# FUSB302-Breakout-ODG_Eagle7_X.net
KiCad netlist of a schematic drawn in EAGLE
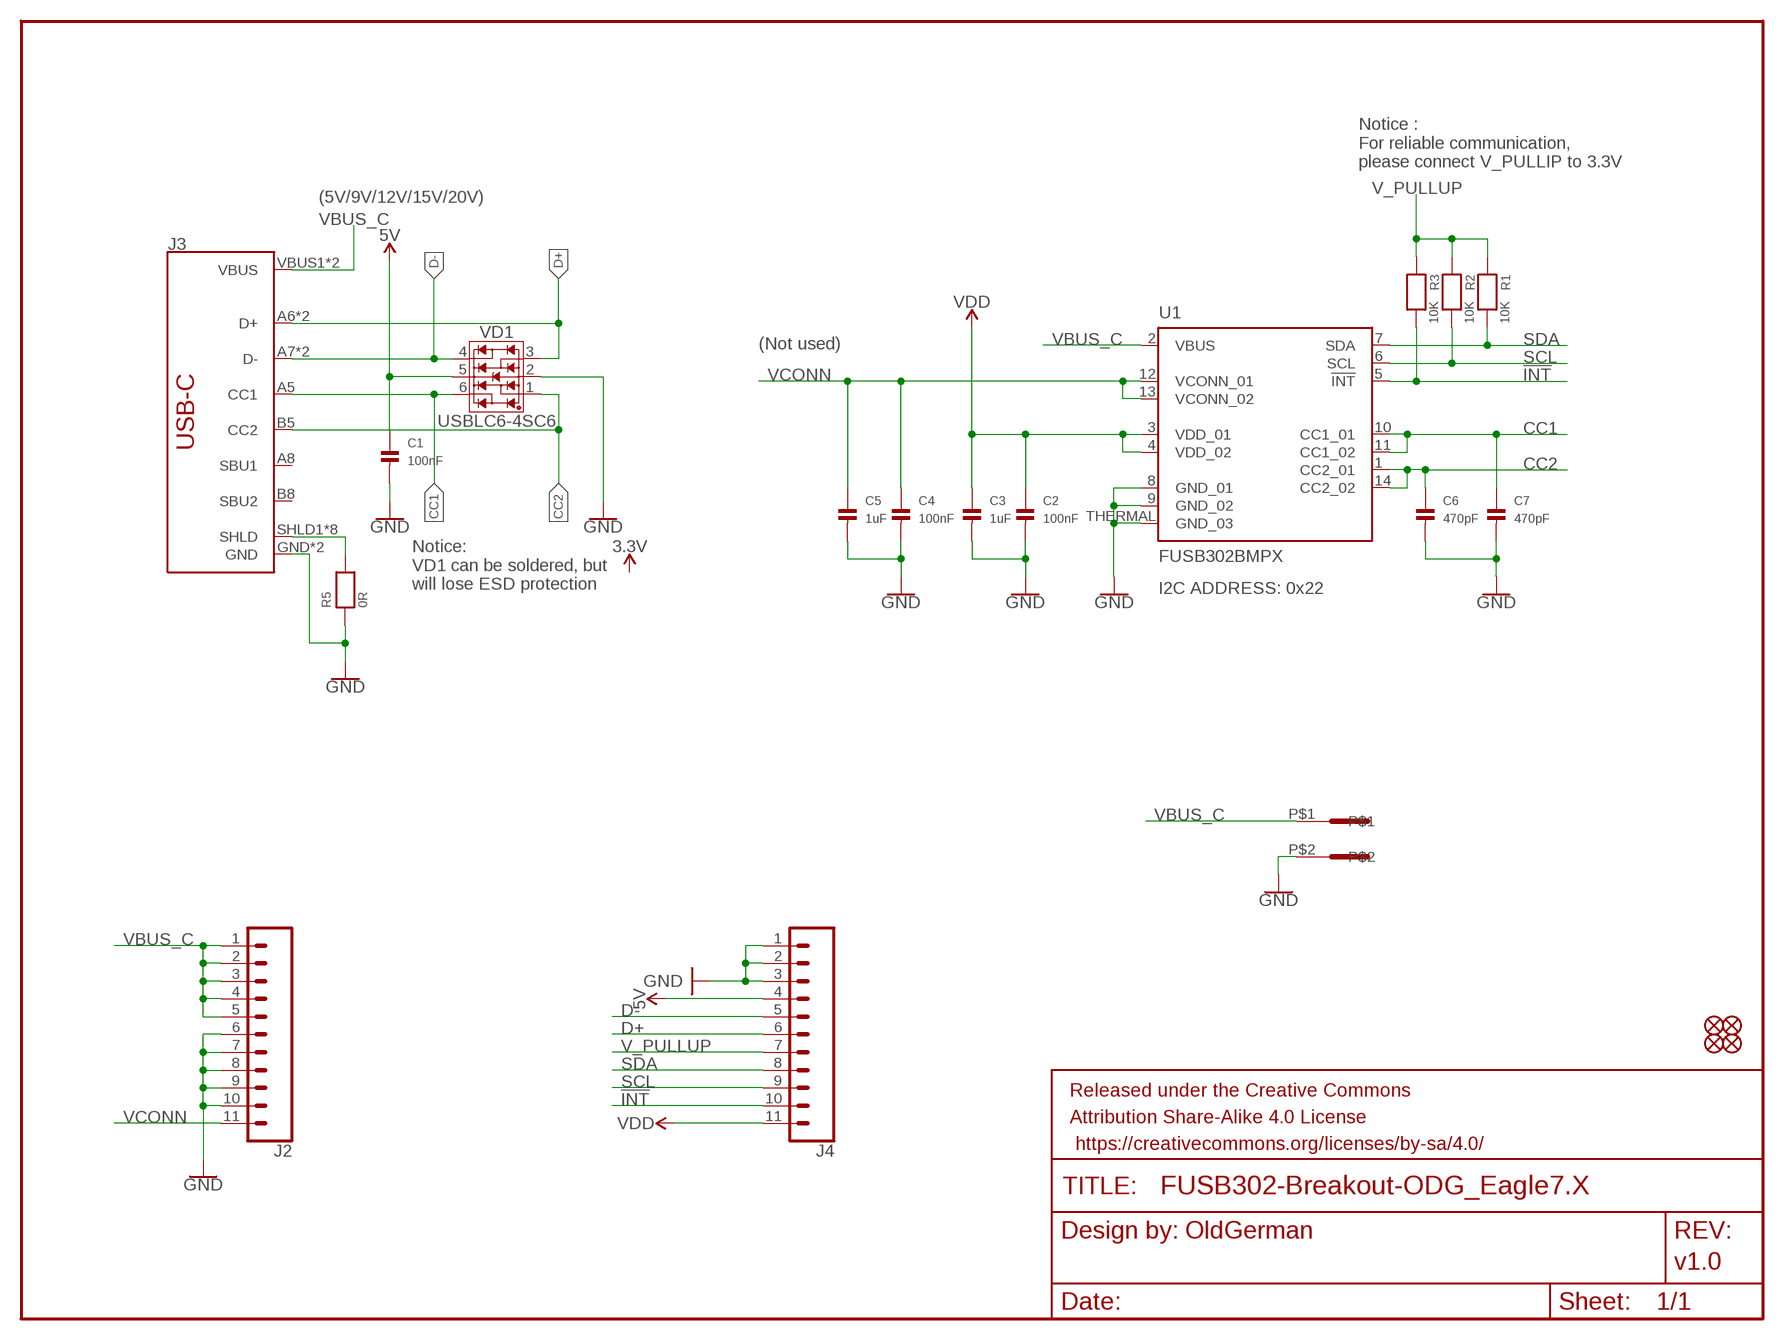
[diagram p0: schematic, sheet 1]

(export (version "E")
  (design (tool "Eeschema 10.0.6"))
  (components
    (comp (ref "C1")
      (value "100nF")
      (footprint "eagle-import:0603")
      (libsource (lib "eagle-import") (part "CAP_CERAMIC0603"))
    )
    (comp (ref "C2")
      (value "100nF")
      (footprint "eagle-import:0603")
      (libsource (lib "eagle-import") (part "CAP_CERAMIC0603"))
    )
    (comp (ref "C3")
      (value "1uF")
      (footprint "eagle-import:0603")
      (libsource (lib "eagle-import") (part "CAP_CERAMIC0603"))
    )
    (comp (ref "C4")
      (value "100nF")
      (footprint "eagle-import:0603")
      (libsource (lib "eagle-import") (part "CAP_CERAMIC0603"))
    )
    (comp (ref "C5")
      (value "1uF")
      (footprint "eagle-import:0603")
      (libsource (lib "eagle-import") (part "CAP_CERAMIC0603"))
    )
    (comp (ref "C6")
      (value "470pF")
      (footprint "eagle-import:0603")
      (libsource (lib "eagle-import") (part "CAP_CERAMIC0603"))
    )
    (comp (ref "C7")
      (value "470pF")
      (footprint "eagle-import:0603")
      (libsource (lib "eagle-import") (part "CAP_CERAMIC0603"))
    )
    (comp (ref "FD5")
      (value "FIDUCIAL_MINI1X2")
      (footprint "eagle-import:FIDUCIAL-1X2")
      (libsource (lib "eagle-import") (part "FIDUCIAL_MINI1X2"))
    )
    (comp (ref "FD6")
      (value "FIDUCIAL_MINI1X2")
      (footprint "eagle-import:FIDUCIAL-1X2")
      (libsource (lib "eagle-import") (part "FIDUCIAL_MINI1X2"))
    )
    (comp (ref "FD7")
      (value "FIDUCIAL_MINI1X2")
      (footprint "eagle-import:FIDUCIAL-1X2")
      (libsource (lib "eagle-import") (part "FIDUCIAL_MINI1X2"))
    )
    (comp (ref "FD8")
      (value "FIDUCIAL_MINI1X2")
      (footprint "eagle-import:FIDUCIAL-1X2")
      (libsource (lib "eagle-import") (part "FIDUCIAL_MINI1X2"))
    )
    (comp (ref "FRAME2")
      (value "FRAME-LETTER")
      (footprint "eagle-import:CREATIVE_COMMONS")
      (libsource (lib "eagle-import") (part "FRAME-LETTER"))
    )
    (comp (ref "J2")
      (value "CONN_11")
      (footprint "eagle-import:1X11")
      (libsource (lib "eagle-import") (part "CONN_11"))
    )
    (comp (ref "J3")
      (value "USB_C_LONG-SYMBOL2-LAYER")
      (footprint "eagle-import:USB-C-16P")
      (libsource (lib "eagle-import") (part "USB_C_LONG-SYMBOL2-LAYER"))
    )
    (comp (ref "J4")
      (value "CONN_11")
      (footprint "eagle-import:1X11")
      (libsource (lib "eagle-import") (part "CONN_11"))
    )
    (comp (ref "R1")
      (value "10K")
      (footprint "eagle-import:0603")
      (libsource (lib "eagle-import") (part "RESISTOR0603"))
    )
    (comp (ref "R2")
      (value "10K")
      (footprint "eagle-import:0603")
      (libsource (lib "eagle-import") (part "RESISTOR0603"))
    )
    (comp (ref "R3")
      (value "10K")
      (footprint "eagle-import:0603")
      (libsource (lib "eagle-import") (part "RESISTOR0603"))
    )
    (comp (ref "R5")
      (value "0R")
      (footprint "eagle-import:0603")
      (libsource (lib "eagle-import") (part "RESISTOR0603"))
    )
    (comp (ref "U$5")
      (value "5.08MM_CONN")
      (footprint "eagle-import:1715250000")
      (libsource (lib "eagle-import") (part "5.08MM_CONN"))
    )
    (comp (ref "U1")
      (value "FUSB302BMPX")
      (footprint "eagle-import:QFN14-2.5X2.5MM")
      (libsource (lib "eagle-import") (part "FUSB302"))
    )
    (comp (ref "VD1")
      (value "USBLC6-4SC6")
      (footprint "eagle-import:SOT23-6")
      (libsource (lib "eagle-import") (part "USBLC6-4SOT23-6"))
    )
  )
  (nets
    (net (code "1") (name "/SCL") (class "Default")
      (node (ref "J4") (pin "9") (pinfunction "9_9") (pintype "passive"))
      (node (ref "R2") (pin "2") (pinfunction "2_2") (pintype "passive"))
      (node (ref "U1") (pin "6") (pinfunction "SCL_6") (pintype "bidirectional"))
    )
    (net (code "2") (name "/SDA") (class "Default")
      (node (ref "J4") (pin "8") (pinfunction "8_8") (pintype "passive"))
      (node (ref "R1") (pin "2") (pinfunction "2_2") (pintype "passive"))
      (node (ref "U1") (pin "7") (pinfunction "SDA_7") (pintype "bidirectional"))
    )
    (net (code "3") (name "/VBUS_C") (class "Default")
      (node (ref "J2") (pin "1") (pinfunction "1_1") (pintype "passive"))
      (node (ref "J2") (pin "2") (pinfunction "2_2") (pintype "passive"))
      (node (ref "J2") (pin "3") (pinfunction "3_3") (pintype "passive"))
      (node (ref "J2") (pin "4") (pinfunction "4_4") (pintype "passive"))
      (node (ref "J2") (pin "5") (pinfunction "5_5") (pintype "passive"))
      (node (ref "J3") (pin "VBUS1") (pinfunction "VBUS_VBUS1") (pintype "bidirectional"))
      (node (ref "J3") (pin "VBUS2") (pinfunction "VBUS_VBUS2") (pintype "bidirectional"))
      (node (ref "U$5") (pin "P$1") (pinfunction "P$1_P$1") (pintype "bidirectional"))
      (node (ref "U1") (pin "2") (pinfunction "VBUS_2") (pintype "bidirectional"))
    )
    (net (code "4") (name "/VCONN") (class "Default")
      (node (ref "C4") (pin "1") (pinfunction "P$1_1") (pintype "passive"))
      (node (ref "C5") (pin "1") (pinfunction "P$1_1") (pintype "passive"))
      (node (ref "J2") (pin "11") (pinfunction "11_11") (pintype "passive"))
      (node (ref "U1") (pin "12") (pinfunction "VCONN_01_12") (pintype "bidirectional"))
      (node (ref "U1") (pin "13") (pinfunction "VCONN_02_13") (pintype "bidirectional"))
    )
    (net (code "5") (name "/V_PULLUP") (class "Default")
      (node (ref "J4") (pin "7") (pinfunction "7_7") (pintype "passive"))
      (node (ref "R1") (pin "1") (pinfunction "1_1") (pintype "passive"))
      (node (ref "R2") (pin "1") (pinfunction "1_1") (pintype "passive"))
      (node (ref "R3") (pin "1") (pinfunction "1_1") (pintype "passive"))
    )
    (net (code "6") (name "/~{INT}") (class "Default")
      (node (ref "J4") (pin "10") (pinfunction "10_10") (pintype "passive"))
      (node (ref "R3") (pin "2") (pinfunction "2_2") (pintype "passive"))
      (node (ref "U1") (pin "5") (pinfunction "~{INT}_5") (pintype "bidirectional"))
    )
    (net (code "8") (name "5V") (class "Default")
      (node (ref "C1") (pin "1") (pinfunction "P$1_1") (pintype "passive"))
      (node (ref "J4") (pin "4") (pinfunction "4_4") (pintype "passive"))
      (node (ref "VD1") (pin "5") (pinfunction "P$5_5") (pintype "bidirectional"))
    )
    (net (code "9") (name "CC1") (class "Default")
      (node (ref "C7") (pin "1") (pinfunction "P$1_1") (pintype "passive"))
      (node (ref "J3") (pin "A5") (pinfunction "CC1_A5") (pintype "bidirectional"))
      (node (ref "U1") (pin "10") (pinfunction "CC1_01_10") (pintype "bidirectional"))
      (node (ref "U1") (pin "11") (pinfunction "CC1_02_11") (pintype "bidirectional"))
      (node (ref "VD1") (pin "6") (pinfunction "P$6_6") (pintype "bidirectional"))
    )
    (net (code "10") (name "CC2") (class "Default")
      (node (ref "C6") (pin "1") (pinfunction "P$1_1") (pintype "passive"))
      (node (ref "J3") (pin "B5") (pinfunction "CC2_B5") (pintype "bidirectional"))
      (node (ref "U1") (pin "1") (pinfunction "CC2_01_1") (pintype "bidirectional"))
      (node (ref "U1") (pin "14") (pinfunction "CC2_02_14") (pintype "bidirectional"))
      (node (ref "VD1") (pin "1") (pinfunction "P$1_1") (pintype "bidirectional"))
    )
    (net (code "11") (name "D+") (class "Default")
      (node (ref "J3") (pin "A6") (pinfunction "D+_A6") (pintype "bidirectional"))
      (node (ref "J3") (pin "B6") (pinfunction "D+_B6") (pintype "bidirectional"))
      (node (ref "J4") (pin "6") (pinfunction "6_6") (pintype "passive"))
      (node (ref "VD1") (pin "3") (pinfunction "P$3_3") (pintype "bidirectional"))
    )
    (net (code "12") (name "D-") (class "Default")
      (node (ref "J3") (pin "A7") (pinfunction "D-_A7") (pintype "bidirectional"))
      (node (ref "J3") (pin "B7") (pinfunction "D-_B7") (pintype "bidirectional"))
      (node (ref "J4") (pin "5") (pinfunction "5_5") (pintype "passive"))
      (node (ref "VD1") (pin "4") (pinfunction "P$4_4") (pintype "bidirectional"))
    )
    (net (code "13") (name "GND") (class "Default")
      (node (ref "C1") (pin "2") (pinfunction "P$2_2") (pintype "passive"))
      (node (ref "C2") (pin "2") (pinfunction "P$2_2") (pintype "passive"))
      (node (ref "C3") (pin "2") (pinfunction "P$2_2") (pintype "passive"))
      (node (ref "C4") (pin "2") (pinfunction "P$2_2") (pintype "passive"))
      (node (ref "C5") (pin "2") (pinfunction "P$2_2") (pintype "passive"))
      (node (ref "C6") (pin "2") (pinfunction "P$2_2") (pintype "passive"))
      (node (ref "C7") (pin "2") (pinfunction "P$2_2") (pintype "passive"))
      (node (ref "J2") (pin "10") (pinfunction "10_10") (pintype "passive"))
      (node (ref "J2") (pin "6") (pinfunction "6_6") (pintype "passive"))
      (node (ref "J2") (pin "7") (pinfunction "7_7") (pintype "passive"))
      (node (ref "J2") (pin "8") (pinfunction "8_8") (pintype "passive"))
      (node (ref "J2") (pin "9") (pinfunction "9_9") (pintype "passive"))
      (node (ref "J3") (pin "GND") (pinfunction "GND_GND") (pintype "bidirectional"))
      (node (ref "J3") (pin "GND2") (pinfunction "GND_GND2") (pintype "bidirectional"))
      (node (ref "J4") (pin "1") (pinfunction "1_1") (pintype "passive"))
      (node (ref "J4") (pin "2") (pinfunction "2_2") (pintype "passive"))
      (node (ref "J4") (pin "3") (pinfunction "3_3") (pintype "passive"))
      (node (ref "R5") (pin "1") (pinfunction "1_1") (pintype "passive"))
      (node (ref "U$5") (pin "P$2") (pinfunction "P$2_P$2") (pintype "bidirectional"))
      (node (ref "U1") (pin "8") (pinfunction "GND_01_8") (pintype "bidirectional"))
      (node (ref "U1") (pin "9") (pinfunction "GND_02_9") (pintype "bidirectional"))
      (node (ref "U1") (pin "THERMAL") (pinfunction "GND_03_THERMAL") (pintype "bidirectional"))
      (node (ref "VD1") (pin "2") (pinfunction "P$2_2") (pintype "bidirectional"))
    )
    (net (code "14") (name "Net-(J3-SHLD-PadSHLD1)") (class "Default")
      (node (ref "J3") (pin "SHLD1") (pinfunction "SHLD_SHLD1") (pintype "bidirectional"))
      (node (ref "J3") (pin "SHLD2") (pinfunction "SHLD_SHLD2") (pintype "bidirectional"))
      (node (ref "J3") (pin "SHLD3") (pinfunction "SHLD_SHLD3") (pintype "bidirectional"))
      (node (ref "J3") (pin "SHLD4") (pinfunction "SHLD_SHLD4") (pintype "bidirectional"))
      (node (ref "J3") (pin "SHLD5") (pinfunction "SHLD_SHLD5") (pintype "bidirectional"))
      (node (ref "J3") (pin "SHLD6") (pinfunction "SHLD_SHLD6") (pintype "bidirectional"))
      (node (ref "J3") (pin "SHLD7") (pinfunction "SHLD_SHLD7") (pintype "bidirectional"))
      (node (ref "J3") (pin "SHLD8") (pinfunction "SHLD_SHLD8") (pintype "bidirectional"))
      (node (ref "R5") (pin "2") (pinfunction "2_2") (pintype "passive"))
    )
    (net (code "15") (name "VDD") (class "Default")
      (node (ref "C2") (pin "1") (pinfunction "P$1_1") (pintype "passive"))
      (node (ref "C3") (pin "1") (pinfunction "P$1_1") (pintype "passive"))
      (node (ref "J4") (pin "11") (pinfunction "11_11") (pintype "passive"))
      (node (ref "U1") (pin "3") (pinfunction "VDD_01_3") (pintype "bidirectional"))
      (node (ref "U1") (pin "4") (pinfunction "VDD_02_4") (pintype "bidirectional"))
    )
    (net (code "16") (name "unconnected-(J3-SBU1-PadA8)") (class "Default")
      (node (ref "J3") (pin "A8") (pinfunction "SBU1_A8") (pintype "bidirectional"))
    )
    (net (code "17") (name "unconnected-(J3-SBU2-PadB8)") (class "Default")
      (node (ref "J3") (pin "B8") (pinfunction "SBU2_B8") (pintype "bidirectional"))
    )
  )
)
